# bolid-inputs-digital.net
KiCad netlist of a schematic drawn in Altium Designer
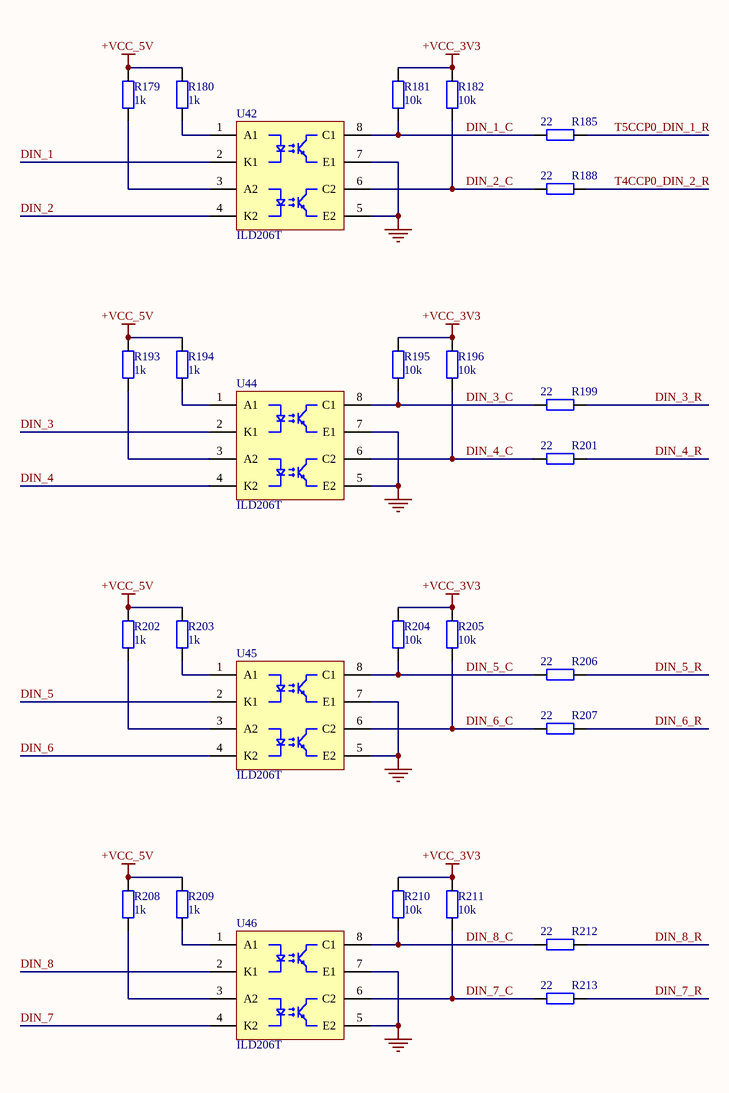
[diagram p0: bolid-inputs-digital.SchDoc]

(export (version "E")
  (design (tool "Eeschema 10.0.6"))
  (components
    (comp (ref "R179")
      (value "1k")
      (footprint "R0402-RESC100X50X40L22N")
      (description "RES 0402 (1005) 1.00k 1% 0.0625W 50V Thick Film")
      (fields
        (field (name "MANUFACTURER") "Yageo")
        (field (name "MANUFACTURER PART NUMBER") "RC0402FR-071KL")
      )
      (libsource (lib "resistors2") (part "RC0402FR-071KL"))
    )
    (comp (ref "R180")
      (value "1k")
      (footprint "R0402-RESC100X50X40L22N")
      (description "RES 0402 (1005) 1.00k 1% 0.0625W 50V Thick Film")
      (fields
        (field (name "MANUFACTURER") "Yageo")
        (field (name "MANUFACTURER PART NUMBER") "RC0402FR-071KL")
      )
      (libsource (lib "resistors2") (part "RC0402FR-071KL"))
    )
    (comp (ref "R181")
      (value "10k")
      (footprint "R0402-RESC100X50X40L22N")
      (description "RES 0402 (1005) 10.0k 1% 0.0625W 50V Thick Film")
      (fields
        (field (name "MANUFACTURER") "Yageo")
        (field (name "MANUFACTURER PART NUMBER") "RC0402FR-0710KL")
      )
      (libsource (lib "resistors2") (part "RC0402FR-0710KL"))
    )
    (comp (ref "R182")
      (value "10k")
      (footprint "R0402-RESC100X50X40L22N")
      (description "RES 0402 (1005) 10.0k 1% 0.0625W 50V Thick Film")
      (fields
        (field (name "MANUFACTURER") "Yageo")
        (field (name "MANUFACTURER PART NUMBER") "RC0402FR-0710KL")
      )
      (libsource (lib "resistors2") (part "RC0402FR-0710KL"))
    )
    (comp (ref "R185")
      (value "22")
      (footprint "R0402-RESC100X50X40L22N")
      (description "RES 0402 (1005) 22.0 ohm 1% 0.0625W 50V Thick Film")
      (fields
        (field (name "MANUFACTURER") "Yageo")
        (field (name "MANUFACTURER PART NUMBER") "RC0402FR-1322RL")
      )
      (libsource (lib "resistors2") (part "RC0402FR-1322RL"))
    )
    (comp (ref "R188")
      (value "22")
      (footprint "R0402-RESC100X50X40L22N")
      (description "RES 0402 (1005) 22.0 ohm 1% 0.0625W 50V Thick Film")
      (fields
        (field (name "MANUFACTURER") "Yageo")
        (field (name "MANUFACTURER PART NUMBER") "RC0402FR-1322RL")
      )
      (libsource (lib "resistors2") (part "RC0402FR-1322RL"))
    )
    (comp (ref "R193")
      (value "1k")
      (footprint "R0402-RESC100X50X40L22N")
      (description "RES 0402 (1005) 1.00k 1% 0.0625W 50V Thick Film")
      (fields
        (field (name "MANUFACTURER") "Yageo")
        (field (name "MANUFACTURER PART NUMBER") "RC0402FR-071KL")
      )
      (libsource (lib "resistors2") (part "RC0402FR-071KL"))
    )
    (comp (ref "R194")
      (value "1k")
      (footprint "R0402-RESC100X50X40L22N")
      (description "RES 0402 (1005) 1.00k 1% 0.0625W 50V Thick Film")
      (fields
        (field (name "MANUFACTURER") "Yageo")
        (field (name "MANUFACTURER PART NUMBER") "RC0402FR-071KL")
      )
      (libsource (lib "resistors2") (part "RC0402FR-071KL"))
    )
    (comp (ref "R195")
      (value "10k")
      (footprint "R0402-RESC100X50X40L22N")
      (description "RES 0402 (1005) 10.0k 1% 0.0625W 50V Thick Film")
      (fields
        (field (name "MANUFACTURER") "Yageo")
        (field (name "MANUFACTURER PART NUMBER") "RC0402FR-0710KL")
      )
      (libsource (lib "resistors2") (part "RC0402FR-0710KL"))
    )
    (comp (ref "R196")
      (value "10k")
      (footprint "R0402-RESC100X50X40L22N")
      (description "RES 0402 (1005) 10.0k 1% 0.0625W 50V Thick Film")
      (fields
        (field (name "MANUFACTURER") "Yageo")
        (field (name "MANUFACTURER PART NUMBER") "RC0402FR-0710KL")
      )
      (libsource (lib "resistors2") (part "RC0402FR-0710KL"))
    )
    (comp (ref "R199")
      (value "22")
      (footprint "R0402-RESC100X50X40L22N")
      (description "RES 0402 (1005) 22.0 ohm 1% 0.0625W 50V Thick Film")
      (fields
        (field (name "MANUFACTURER") "Yageo")
        (field (name "MANUFACTURER PART NUMBER") "RC0402FR-1322RL")
      )
      (libsource (lib "resistors2") (part "RC0402FR-1322RL"))
    )
    (comp (ref "R201")
      (value "22")
      (footprint "R0402-RESC100X50X40L22N")
      (description "RES 0402 (1005) 22.0 ohm 1% 0.0625W 50V Thick Film")
      (fields
        (field (name "MANUFACTURER") "Yageo")
        (field (name "MANUFACTURER PART NUMBER") "RC0402FR-1322RL")
      )
      (libsource (lib "resistors2") (part "RC0402FR-1322RL"))
    )
    (comp (ref "R202")
      (value "1k")
      (footprint "R0402-RESC100X50X40L22N")
      (description "RES 0402 (1005) 1.00k 1% 0.0625W 50V Thick Film")
      (fields
        (field (name "MANUFACTURER") "Yageo")
        (field (name "MANUFACTURER PART NUMBER") "RC0402FR-071KL")
      )
      (libsource (lib "resistors2") (part "RC0402FR-071KL"))
    )
    (comp (ref "R203")
      (value "1k")
      (footprint "R0402-RESC100X50X40L22N")
      (description "RES 0402 (1005) 1.00k 1% 0.0625W 50V Thick Film")
      (fields
        (field (name "MANUFACTURER") "Yageo")
        (field (name "MANUFACTURER PART NUMBER") "RC0402FR-071KL")
      )
      (libsource (lib "resistors2") (part "RC0402FR-071KL"))
    )
    (comp (ref "R204")
      (value "10k")
      (footprint "R0402-RESC100X50X40L22N")
      (description "RES 0402 (1005) 10.0k 1% 0.0625W 50V Thick Film")
      (fields
        (field (name "MANUFACTURER") "Yageo")
        (field (name "MANUFACTURER PART NUMBER") "RC0402FR-0710KL")
      )
      (libsource (lib "resistors2") (part "RC0402FR-0710KL"))
    )
    (comp (ref "R205")
      (value "10k")
      (footprint "R0402-RESC100X50X40L22N")
      (description "RES 0402 (1005) 10.0k 1% 0.0625W 50V Thick Film")
      (fields
        (field (name "MANUFACTURER") "Yageo")
        (field (name "MANUFACTURER PART NUMBER") "RC0402FR-0710KL")
      )
      (libsource (lib "resistors2") (part "RC0402FR-0710KL"))
    )
    (comp (ref "R206")
      (value "22")
      (footprint "R0402-RESC100X50X40L22N")
      (description "RES 0402 (1005) 22.0 ohm 1% 0.0625W 50V Thick Film")
      (fields
        (field (name "MANUFACTURER") "Yageo")
        (field (name "MANUFACTURER PART NUMBER") "RC0402FR-1322RL")
      )
      (libsource (lib "resistors2") (part "RC0402FR-1322RL"))
    )
    (comp (ref "R207")
      (value "22")
      (footprint "R0402-RESC100X50X40L22N")
      (description "RES 0402 (1005) 22.0 ohm 1% 0.0625W 50V Thick Film")
      (fields
        (field (name "MANUFACTURER") "Yageo")
        (field (name "MANUFACTURER PART NUMBER") "RC0402FR-1322RL")
      )
      (libsource (lib "resistors2") (part "RC0402FR-1322RL"))
    )
    (comp (ref "R208")
      (value "1k")
      (footprint "R0402-RESC100X50X40L22N")
      (description "RES 0402 (1005) 1.00k 1% 0.0625W 50V Thick Film")
      (fields
        (field (name "MANUFACTURER") "Yageo")
        (field (name "MANUFACTURER PART NUMBER") "RC0402FR-071KL")
      )
      (libsource (lib "resistors2") (part "RC0402FR-071KL"))
    )
    (comp (ref "R209")
      (value "1k")
      (footprint "R0402-RESC100X50X40L22N")
      (description "RES 0402 (1005) 1.00k 1% 0.0625W 50V Thick Film")
      (fields
        (field (name "MANUFACTURER") "Yageo")
        (field (name "MANUFACTURER PART NUMBER") "RC0402FR-071KL")
      )
      (libsource (lib "resistors2") (part "RC0402FR-071KL"))
    )
    (comp (ref "R210")
      (value "10k")
      (footprint "R0402-RESC100X50X40L22N")
      (description "RES 0402 (1005) 10.0k 1% 0.0625W 50V Thick Film")
      (fields
        (field (name "MANUFACTURER") "Yageo")
        (field (name "MANUFACTURER PART NUMBER") "RC0402FR-0710KL")
      )
      (libsource (lib "resistors2") (part "RC0402FR-0710KL"))
    )
    (comp (ref "R211")
      (value "10k")
      (footprint "R0402-RESC100X50X40L22N")
      (description "RES 0402 (1005) 10.0k 1% 0.0625W 50V Thick Film")
      (fields
        (field (name "MANUFACTURER") "Yageo")
        (field (name "MANUFACTURER PART NUMBER") "RC0402FR-0710KL")
      )
      (libsource (lib "resistors2") (part "RC0402FR-0710KL"))
    )
    (comp (ref "R212")
      (value "22")
      (footprint "R0402-RESC100X50X40L22N")
      (description "RES 0402 (1005) 22.0 ohm 1% 0.0625W 50V Thick Film")
      (fields
        (field (name "MANUFACTURER") "Yageo")
        (field (name "MANUFACTURER PART NUMBER") "RC0402FR-1322RL")
      )
      (libsource (lib "resistors2") (part "RC0402FR-1322RL"))
    )
    (comp (ref "R213")
      (value "22")
      (footprint "R0402-RESC100X50X40L22N")
      (description "RES 0402 (1005) 22.0 ohm 1% 0.0625W 50V Thick Film")
      (fields
        (field (name "MANUFACTURER") "Yageo")
        (field (name "MANUFACTURER PART NUMBER") "RC0402FR-1322RL")
      )
      (libsource (lib "resistors2") (part "RC0402FR-1322RL"))
    )
    (comp (ref "U42")
      (value "ILD206T")
      (footprint "Vishay SOIC8 ILD SOIC8P127_600X610X395L51X41")
      (description "Transistor Output Optocouplers Phototransistor Out Dual CTR 63-125%")
      (fields (field (name "MANUFACTURER") "Vishay Semiconductors"))
      (libsource (lib "semiconductors2") (part "ILD206T"))
    )
    (comp (ref "U44")
      (value "ILD206T")
      (footprint "Vishay SOIC8 ILD SOIC8P127_600X610X395L51X41")
      (description "Transistor Output Optocouplers Phototransistor Out Dual CTR 63-125%")
      (fields (field (name "MANUFACTURER") "Vishay Semiconductors"))
      (libsource (lib "semiconductors2") (part "ILD206T"))
    )
    (comp (ref "U45")
      (value "ILD206T")
      (footprint "Vishay SOIC8 ILD SOIC8P127_600X610X395L51X41")
      (description "Transistor Output Optocouplers Phototransistor Out Dual CTR 63-125%")
      (fields (field (name "MANUFACTURER") "Vishay Semiconductors"))
      (libsource (lib "semiconductors2") (part "ILD206T"))
    )
    (comp (ref "U46")
      (value "ILD206T")
      (footprint "Vishay SOIC8 ILD SOIC8P127_600X610X395L51X41")
      (description "Transistor Output Optocouplers Phototransistor Out Dual CTR 63-125%")
      (fields (field (name "MANUFACTURER") "Vishay Semiconductors"))
      (libsource (lib "semiconductors2") (part "ILD206T"))
    )
  )
  (nets
    (net (code "1") (name "+VCC_3V3") (class "Default")
      (node (ref "R181") (pin "2") (pinfunction "2_2") (pintype "passive"))
      (node (ref "R182") (pin "2") (pinfunction "2_2") (pintype "passive"))
      (node (ref "R195") (pin "2") (pinfunction "2_2") (pintype "passive"))
      (node (ref "R196") (pin "2") (pinfunction "2_2") (pintype "passive"))
      (node (ref "R204") (pin "2") (pinfunction "2_2") (pintype "passive"))
      (node (ref "R205") (pin "2") (pinfunction "2_2") (pintype "passive"))
      (node (ref "R210") (pin "2") (pinfunction "2_2") (pintype "passive"))
      (node (ref "R211") (pin "2") (pinfunction "2_2") (pintype "passive"))
    )
    (net (code "2") (name "+VCC_5V") (class "Default")
      (node (ref "R179") (pin "2") (pinfunction "2_2") (pintype "passive"))
      (node (ref "R180") (pin "2") (pinfunction "2_2") (pintype "passive"))
      (node (ref "R193") (pin "2") (pinfunction "2_2") (pintype "passive"))
      (node (ref "R194") (pin "2") (pinfunction "2_2") (pintype "passive"))
      (node (ref "R202") (pin "2") (pinfunction "2_2") (pintype "passive"))
      (node (ref "R203") (pin "2") (pinfunction "2_2") (pintype "passive"))
      (node (ref "R208") (pin "2") (pinfunction "2_2") (pintype "passive"))
      (node (ref "R209") (pin "2") (pinfunction "2_2") (pintype "passive"))
    )
    (net (code "3") (name "/DIN_1") (class "Default")
      (node (ref "U42") (pin "2") (pinfunction "K1_2") (pintype "passive"))
    )
    (net (code "4") (name "/DIN_1_C") (class "Default")
      (node (ref "R181") (pin "1") (pinfunction "1_1") (pintype "passive"))
      (node (ref "R185") (pin "1") (pinfunction "1_1") (pintype "passive"))
      (node (ref "U42") (pin "8") (pinfunction "C1_8") (pintype "passive"))
    )
    (net (code "5") (name "/DIN_2") (class "Default")
      (node (ref "U42") (pin "4") (pinfunction "K2_4") (pintype "passive"))
    )
    (net (code "6") (name "/DIN_2_C") (class "Default")
      (node (ref "R182") (pin "1") (pinfunction "1_1") (pintype "passive"))
      (node (ref "R188") (pin "1") (pinfunction "1_1") (pintype "passive"))
      (node (ref "U42") (pin "6") (pinfunction "C2_6") (pintype "passive"))
    )
    (net (code "7") (name "/DIN_3") (class "Default")
      (node (ref "U44") (pin "2") (pinfunction "K1_2") (pintype "passive"))
    )
    (net (code "8") (name "/DIN_3_C") (class "Default")
      (node (ref "R195") (pin "1") (pinfunction "1_1") (pintype "passive"))
      (node (ref "R199") (pin "1") (pinfunction "1_1") (pintype "passive"))
      (node (ref "U44") (pin "8") (pinfunction "C1_8") (pintype "passive"))
    )
    (net (code "9") (name "/DIN_3_R") (class "Default")
      (node (ref "R199") (pin "2") (pinfunction "2_2") (pintype "passive"))
    )
    (net (code "10") (name "/DIN_4") (class "Default")
      (node (ref "U44") (pin "4") (pinfunction "K2_4") (pintype "passive"))
    )
    (net (code "11") (name "/DIN_4_C") (class "Default")
      (node (ref "R196") (pin "1") (pinfunction "1_1") (pintype "passive"))
      (node (ref "R201") (pin "1") (pinfunction "1_1") (pintype "passive"))
      (node (ref "U44") (pin "6") (pinfunction "C2_6") (pintype "passive"))
    )
    (net (code "12") (name "/DIN_4_R") (class "Default")
      (node (ref "R201") (pin "2") (pinfunction "2_2") (pintype "passive"))
    )
    (net (code "13") (name "/DIN_5") (class "Default")
      (node (ref "U45") (pin "2") (pinfunction "K1_2") (pintype "passive"))
    )
    (net (code "14") (name "/DIN_5_C") (class "Default")
      (node (ref "R204") (pin "1") (pinfunction "1_1") (pintype "passive"))
      (node (ref "R206") (pin "1") (pinfunction "1_1") (pintype "passive"))
      (node (ref "U45") (pin "8") (pinfunction "C1_8") (pintype "passive"))
    )
    (net (code "15") (name "/DIN_5_R") (class "Default")
      (node (ref "R206") (pin "2") (pinfunction "2_2") (pintype "passive"))
    )
    (net (code "16") (name "/DIN_6") (class "Default")
      (node (ref "U45") (pin "4") (pinfunction "K2_4") (pintype "passive"))
    )
    (net (code "17") (name "/DIN_6_C") (class "Default")
      (node (ref "R205") (pin "1") (pinfunction "1_1") (pintype "passive"))
      (node (ref "R207") (pin "1") (pinfunction "1_1") (pintype "passive"))
      (node (ref "U45") (pin "6") (pinfunction "C2_6") (pintype "passive"))
    )
    (net (code "18") (name "/DIN_6_R") (class "Default")
      (node (ref "R207") (pin "2") (pinfunction "2_2") (pintype "passive"))
    )
    (net (code "19") (name "/DIN_7") (class "Default")
      (node (ref "U46") (pin "4") (pinfunction "K2_4") (pintype "passive"))
    )
    (net (code "20") (name "/DIN_7_C") (class "Default")
      (node (ref "R211") (pin "1") (pinfunction "1_1") (pintype "passive"))
      (node (ref "R213") (pin "1") (pinfunction "1_1") (pintype "passive"))
      (node (ref "U46") (pin "6") (pinfunction "C2_6") (pintype "passive"))
    )
    (net (code "21") (name "/DIN_7_R") (class "Default")
      (node (ref "R213") (pin "2") (pinfunction "2_2") (pintype "passive"))
    )
    (net (code "22") (name "/DIN_8") (class "Default")
      (node (ref "U46") (pin "2") (pinfunction "K1_2") (pintype "passive"))
    )
    (net (code "23") (name "/DIN_8_C") (class "Default")
      (node (ref "R210") (pin "1") (pinfunction "1_1") (pintype "passive"))
      (node (ref "R212") (pin "1") (pinfunction "1_1") (pintype "passive"))
      (node (ref "U46") (pin "8") (pinfunction "C1_8") (pintype "passive"))
    )
    (net (code "24") (name "/DIN_8_R") (class "Default")
      (node (ref "R212") (pin "2") (pinfunction "2_2") (pintype "passive"))
    )
    (net (code "25") (name "/T4CCP0_DIN_2_R") (class "Default")
      (node (ref "R188") (pin "2") (pinfunction "2_2") (pintype "passive"))
    )
    (net (code "26") (name "/T5CCP0_DIN_1_R") (class "Default")
      (node (ref "R185") (pin "2") (pinfunction "2_2") (pintype "passive"))
    )
    (net (code "27") (name "GND") (class "Default")
      (node (ref "U42") (pin "5") (pinfunction "E2_5") (pintype "passive"))
      (node (ref "U42") (pin "7") (pinfunction "E1_7") (pintype "passive"))
      (node (ref "U44") (pin "5") (pinfunction "E2_5") (pintype "passive"))
      (node (ref "U44") (pin "7") (pinfunction "E1_7") (pintype "passive"))
      (node (ref "U45") (pin "5") (pinfunction "E2_5") (pintype "passive"))
      (node (ref "U45") (pin "7") (pinfunction "E1_7") (pintype "passive"))
      (node (ref "U46") (pin "5") (pinfunction "E2_5") (pintype "passive"))
      (node (ref "U46") (pin "7") (pinfunction "E1_7") (pintype "passive"))
    )
    (net (code "28") (name "Net-(U42-A1)") (class "Default")
      (node (ref "R180") (pin "1") (pinfunction "1_1") (pintype "passive"))
      (node (ref "U42") (pin "1") (pinfunction "A1_1") (pintype "passive"))
    )
    (net (code "29") (name "Net-(U42-A2)") (class "Default")
      (node (ref "R179") (pin "1") (pinfunction "1_1") (pintype "passive"))
      (node (ref "U42") (pin "3") (pinfunction "A2_3") (pintype "passive"))
    )
    (net (code "30") (name "Net-(U44-A1)") (class "Default")
      (node (ref "R194") (pin "1") (pinfunction "1_1") (pintype "passive"))
      (node (ref "U44") (pin "1") (pinfunction "A1_1") (pintype "passive"))
    )
    (net (code "31") (name "Net-(U44-A2)") (class "Default")
      (node (ref "R193") (pin "1") (pinfunction "1_1") (pintype "passive"))
      (node (ref "U44") (pin "3") (pinfunction "A2_3") (pintype "passive"))
    )
    (net (code "32") (name "Net-(U45-A1)") (class "Default")
      (node (ref "R203") (pin "1") (pinfunction "1_1") (pintype "passive"))
      (node (ref "U45") (pin "1") (pinfunction "A1_1") (pintype "passive"))
    )
    (net (code "33") (name "Net-(U45-A2)") (class "Default")
      (node (ref "R202") (pin "1") (pinfunction "1_1") (pintype "passive"))
      (node (ref "U45") (pin "3") (pinfunction "A2_3") (pintype "passive"))
    )
    (net (code "34") (name "Net-(U46-A1)") (class "Default")
      (node (ref "R209") (pin "1") (pinfunction "1_1") (pintype "passive"))
      (node (ref "U46") (pin "1") (pinfunction "A1_1") (pintype "passive"))
    )
    (net (code "35") (name "Net-(U46-A2)") (class "Default")
      (node (ref "R208") (pin "1") (pinfunction "1_1") (pintype "passive"))
      (node (ref "U46") (pin "3") (pinfunction "A2_3") (pintype "passive"))
    )
  )
)
